# schematics.net
KiCad netlist of a schematic drawn in EAGLE
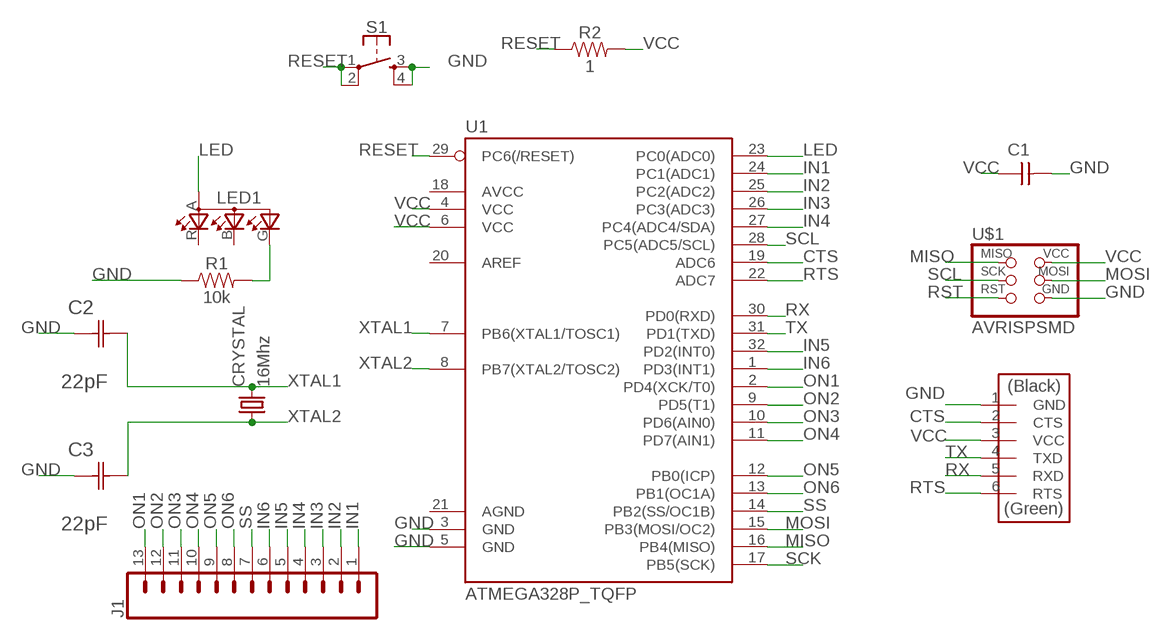
[diagram p0: schematic, sheet 1]

(export (version "E")
  (design (tool "Eeschema 10.0.6"))
  (components
    (comp (ref "C1")
      (value "CAP-UNPOLARIZEDFAB")
      (footprint "eagle-import:C1206FAB")
      (libsource (lib "eagle-import") (part "CAP-UNPOLARIZEDFAB"))
    )
    (comp (ref "C2")
      (value "22pF")
      (footprint "eagle-import:CAPC3216X178N")
      (fields (field (name "MPN") "0612ZC225MAT2A") (field (name "TOLERANCE") "±20%"))
      (libsource (lib "eagle-import") (part "0612ZC225MAT2A"))
    )
    (comp (ref "C3")
      (value "22pF")
      (footprint "eagle-import:CAPC3216X178N")
      (fields (field (name "MPN") "0612ZC225MAT2A") (field (name "TOLERANCE") "±20%"))
      (libsource (lib "eagle-import") (part "0612ZC225MAT2A"))
    )
    (comp (ref "CRYSTAL")
      (value "16Mhz")
      (footprint "eagle-import:CSM-7X-DU")
      (libsource (lib "eagle-import") (part "CSM-7X-DU"))
    )
    (comp (ref "J1")
      (value "CONN_13")
      (footprint "eagle-import:1X13")
      (libsource (lib "eagle-import") (part "CONN_13"))
    )
    (comp (ref "LED1")
      (value "LEDRGBOLD")
      (footprint "eagle-import:P-LCC-4-3")
      (libsource (lib "eagle-import") (part "LEDRGBOLD"))
    )
    (comp (ref "R1")
      (value "10k")
      (footprint "eagle-import:0603")
      (libsource (lib "eagle-import") (part "10KOHM-0603-1/10W-1%"))
    )
    (comp (ref "R2")
      (value "1")
      (footprint "eagle-import:0603")
      (libsource (lib "eagle-import") (part "1OHM-0603-1/10W-1%"))
    )
    (comp (ref "S1")
      (value "MOMENTARY-SWITCH-SPST-2-SMD-4.6X2.8MM")
      (footprint "eagle-import:TACTILE_SWITCH_SMD_4.6X2.8MM")
      (libsource (lib "eagle-import") (part "MOMENTARY-SWITCH-SPST-2-SMD-4.6X2.8MM"))
    )
    (comp (ref "U$1")
      (value "AVRISPSMD")
      (footprint "eagle-import:2X03SMD")
      (libsource (lib "eagle-import") (part "AVRISPSMD"))
    )
    (comp (ref "U$2")
      (value "FTDI-SMD-HEADER")
      (footprint "eagle-import:1X06SMD")
      (libsource (lib "eagle-import") (part "FTDI-SMD-HEADER"))
    )
    (comp (ref "U1")
      (value "ATMEGA328P_TQFP")
      (footprint "eagle-import:TQFP32-08")
      (libsource (lib "eagle-import") (part "ATMEGA328P_TQFP"))
    )
  )
  (nets
    (net (code "1") (name "/CTS") (class "Default")
      (node (ref "U$2") (pin "2") (pinfunction "CTS_2") (pintype "bidirectional"))
      (node (ref "U1") (pin "19") (pinfunction "ADC6_19") (pintype "bidirectional"))
    )
    (net (code "2") (name "/GND") (class "Default")
      (node (ref "C1") (pin "2") (pinfunction "2_2") (pintype "passive"))
      (node (ref "C2") (pin "1") (pinfunction "C1_1") (pintype "passive"))
      (node (ref "C3") (pin "1") (pinfunction "C1_1") (pintype "passive"))
      (node (ref "R1") (pin "1") (pinfunction "1_1") (pintype "passive"))
      (node (ref "S1") (pin "3") (pinfunction "3_3") (pintype "passive"))
      (node (ref "S1") (pin "4") (pinfunction "4_4") (pintype "passive"))
      (node (ref "U$1") (pin "6") (pinfunction "GND_6") (pintype "passive"))
      (node (ref "U$2") (pin "1") (pinfunction "GND_1") (pintype "bidirectional"))
      (node (ref "U1") (pin "3") (pinfunction "GND_3") (pintype "bidirectional"))
      (node (ref "U1") (pin "5") (pinfunction "GND_5") (pintype "bidirectional"))
    )
    (net (code "3") (name "/IN1") (class "Default")
      (node (ref "J1") (pin "1") (pinfunction "1_1") (pintype "passive"))
      (node (ref "U1") (pin "24") (pinfunction "PC1(ADC1)_24") (pintype "bidirectional"))
    )
    (net (code "4") (name "/IN2") (class "Default")
      (node (ref "J1") (pin "2") (pinfunction "2_2") (pintype "passive"))
      (node (ref "U1") (pin "25") (pinfunction "PC2(ADC2)_25") (pintype "bidirectional"))
    )
    (net (code "5") (name "/IN3") (class "Default")
      (node (ref "J1") (pin "3") (pinfunction "3_3") (pintype "passive"))
      (node (ref "U1") (pin "26") (pinfunction "PC3(ADC3)_26") (pintype "bidirectional"))
    )
    (net (code "6") (name "/IN4") (class "Default")
      (node (ref "J1") (pin "4") (pinfunction "4_4") (pintype "passive"))
      (node (ref "U1") (pin "27") (pinfunction "PC4(ADC4/SDA)_27") (pintype "bidirectional"))
    )
    (net (code "7") (name "/IN5") (class "Default")
      (node (ref "J1") (pin "5") (pinfunction "5_5") (pintype "passive"))
      (node (ref "U1") (pin "32") (pinfunction "PD2(INT0)_32") (pintype "bidirectional"))
    )
    (net (code "8") (name "/IN6") (class "Default")
      (node (ref "J1") (pin "6") (pinfunction "6_6") (pintype "passive"))
      (node (ref "U1") (pin "1") (pinfunction "PD3(INT1)_1") (pintype "bidirectional"))
    )
    (net (code "9") (name "/LED") (class "Default")
      (node (ref "LED1") (pin "A") (pinfunction "A2_A") (pintype "passive"))
      (node (ref "U1") (pin "23") (pinfunction "PC0(ADC0)_23") (pintype "bidirectional"))
    )
    (net (code "10") (name "/MISO") (class "Default")
      (node (ref "U$1") (pin "1") (pinfunction "MISO_1") (pintype "passive"))
      (node (ref "U1") (pin "16") (pinfunction "PB4(MISO)_16") (pintype "bidirectional"))
    )
    (net (code "11") (name "/MOSI") (class "Default")
      (node (ref "U$1") (pin "4") (pinfunction "MOSI_4") (pintype "passive"))
      (node (ref "U1") (pin "15") (pinfunction "PB3(MOSI/OC2)_15") (pintype "bidirectional"))
    )
    (net (code "12") (name "/ON1") (class "Default")
      (node (ref "J1") (pin "13") (pinfunction "13_13") (pintype "passive"))
      (node (ref "U1") (pin "2") (pinfunction "PD4(XCK/T0)_2") (pintype "bidirectional"))
    )
    (net (code "13") (name "/ON2") (class "Default")
      (node (ref "J1") (pin "12") (pinfunction "12_12") (pintype "passive"))
      (node (ref "U1") (pin "9") (pinfunction "PD5(T1)_9") (pintype "bidirectional"))
    )
    (net (code "14") (name "/ON3") (class "Default")
      (node (ref "J1") (pin "11") (pinfunction "11_11") (pintype "passive"))
      (node (ref "U1") (pin "10") (pinfunction "PD6(AIN0)_10") (pintype "bidirectional"))
    )
    (net (code "15") (name "/ON4") (class "Default")
      (node (ref "J1") (pin "10") (pinfunction "10_10") (pintype "passive"))
      (node (ref "U1") (pin "11") (pinfunction "PD7(AIN1)_11") (pintype "bidirectional"))
    )
    (net (code "16") (name "/ON5") (class "Default")
      (node (ref "J1") (pin "9") (pinfunction "9_9") (pintype "passive"))
      (node (ref "U1") (pin "12") (pinfunction "PB0(ICP)_12") (pintype "bidirectional"))
    )
    (net (code "17") (name "/ON6") (class "Default")
      (node (ref "J1") (pin "8") (pinfunction "8_8") (pintype "passive"))
      (node (ref "U1") (pin "13") (pinfunction "PB1(OC1A)_13") (pintype "bidirectional"))
    )
    (net (code "18") (name "/RESET") (class "Default")
      (node (ref "R2") (pin "1") (pinfunction "1_1") (pintype "passive"))
      (node (ref "S1") (pin "1") (pinfunction "1_1") (pintype "passive"))
      (node (ref "S1") (pin "2") (pinfunction "2_2") (pintype "passive"))
      (node (ref "U1") (pin "29") (pinfunction "PC6(/RESET)_29") (pintype "bidirectional"))
    )
    (net (code "19") (name "/RST") (class "Default")
      (node (ref "U$1") (pin "5") (pinfunction "RST_5") (pintype "passive"))
    )
    (net (code "20") (name "/RTS") (class "Default")
      (node (ref "U$2") (pin "6") (pinfunction "RTS_6") (pintype "bidirectional"))
      (node (ref "U1") (pin "22") (pinfunction "ADC7_22") (pintype "bidirectional"))
    )
    (net (code "21") (name "/RX") (class "Default")
      (node (ref "U$2") (pin "5") (pinfunction "RXD_5") (pintype "bidirectional"))
      (node (ref "U1") (pin "30") (pinfunction "PD0(RXD)_30") (pintype "bidirectional"))
    )
    (net (code "22") (name "/SCK") (class "Default")
      (node (ref "U1") (pin "17") (pinfunction "PB5(SCK)_17") (pintype "bidirectional"))
    )
    (net (code "23") (name "/SCL") (class "Default")
      (node (ref "U$1") (pin "3") (pinfunction "SCK_3") (pintype "passive"))
      (node (ref "U1") (pin "28") (pinfunction "PC5(ADC5/SCL)_28") (pintype "bidirectional"))
    )
    (net (code "24") (name "/SS") (class "Default")
      (node (ref "J1") (pin "7") (pinfunction "7_7") (pintype "passive"))
      (node (ref "U1") (pin "14") (pinfunction "PB2(SS/OC1B)_14") (pintype "bidirectional"))
    )
    (net (code "25") (name "/TX") (class "Default")
      (node (ref "U$2") (pin "4") (pinfunction "TXD_4") (pintype "bidirectional"))
      (node (ref "U1") (pin "31") (pinfunction "PD1(TXD)_31") (pintype "bidirectional"))
    )
    (net (code "26") (name "/VCC") (class "Default")
      (node (ref "C1") (pin "1") (pinfunction "1_1") (pintype "passive"))
      (node (ref "R2") (pin "2") (pinfunction "2_2") (pintype "passive"))
      (node (ref "U$1") (pin "2") (pinfunction "VCC_2") (pintype "passive"))
      (node (ref "U$2") (pin "3") (pinfunction "VCC_3") (pintype "bidirectional"))
      (node (ref "U1") (pin "4") (pinfunction "VCC_4") (pintype "bidirectional"))
      (node (ref "U1") (pin "6") (pinfunction "VCC_6") (pintype "bidirectional"))
    )
    (net (code "27") (name "/XTAL1") (class "Default")
      (node (ref "C2") (pin "2") (pinfunction "C2_2") (pintype "passive"))
      (node (ref "CRYSTAL") (pin "2") (pinfunction "2_2") (pintype "passive"))
      (node (ref "U1") (pin "7") (pinfunction "PB6(XTAL1/TOSC1)_7") (pintype "bidirectional"))
    )
    (net (code "28") (name "/XTAL2") (class "Default")
      (node (ref "C3") (pin "2") (pinfunction "C2_2") (pintype "passive"))
      (node (ref "CRYSTAL") (pin "1") (pinfunction "1_1") (pintype "passive"))
      (node (ref "U1") (pin "8") (pinfunction "PB7(XTAL2/TOSC2)_8") (pintype "bidirectional"))
    )
    (net (code "29") (name "Net-(LED1-CGREEN)") (class "Default")
      (node (ref "LED1") (pin "G") (pinfunction "CGREEN_G") (pintype "passive"))
      (node (ref "R1") (pin "2") (pinfunction "2_2") (pintype "passive"))
    )
    (net (code "30") (name "unconnected-(LED1-CBLUE-PadB)") (class "Default")
      (node (ref "LED1") (pin "B") (pinfunction "CBLUE_B") (pintype "passive"))
    )
    (net (code "31") (name "unconnected-(LED1-CRED-PadR)") (class "Default")
      (node (ref "LED1") (pin "R") (pinfunction "CRED_R") (pintype "passive"))
    )
    (net (code "32") (name "unconnected-(U1-AGND-Pad21)") (class "Default")
      (node (ref "U1") (pin "21") (pinfunction "AGND_21") (pintype "bidirectional"))
    )
    (net (code "33") (name "unconnected-(U1-AREF-Pad20)") (class "Default")
      (node (ref "U1") (pin "20") (pinfunction "AREF_20") (pintype "bidirectional"))
    )
    (net (code "34") (name "unconnected-(U1-AVCC-Pad18)") (class "Default")
      (node (ref "U1") (pin "18") (pinfunction "AVCC_18") (pintype "bidirectional"))
    )
  )
)
